# tinyduino-breakout-mk-4_3.net
KiCad netlist of a schematic drawn in EAGLE
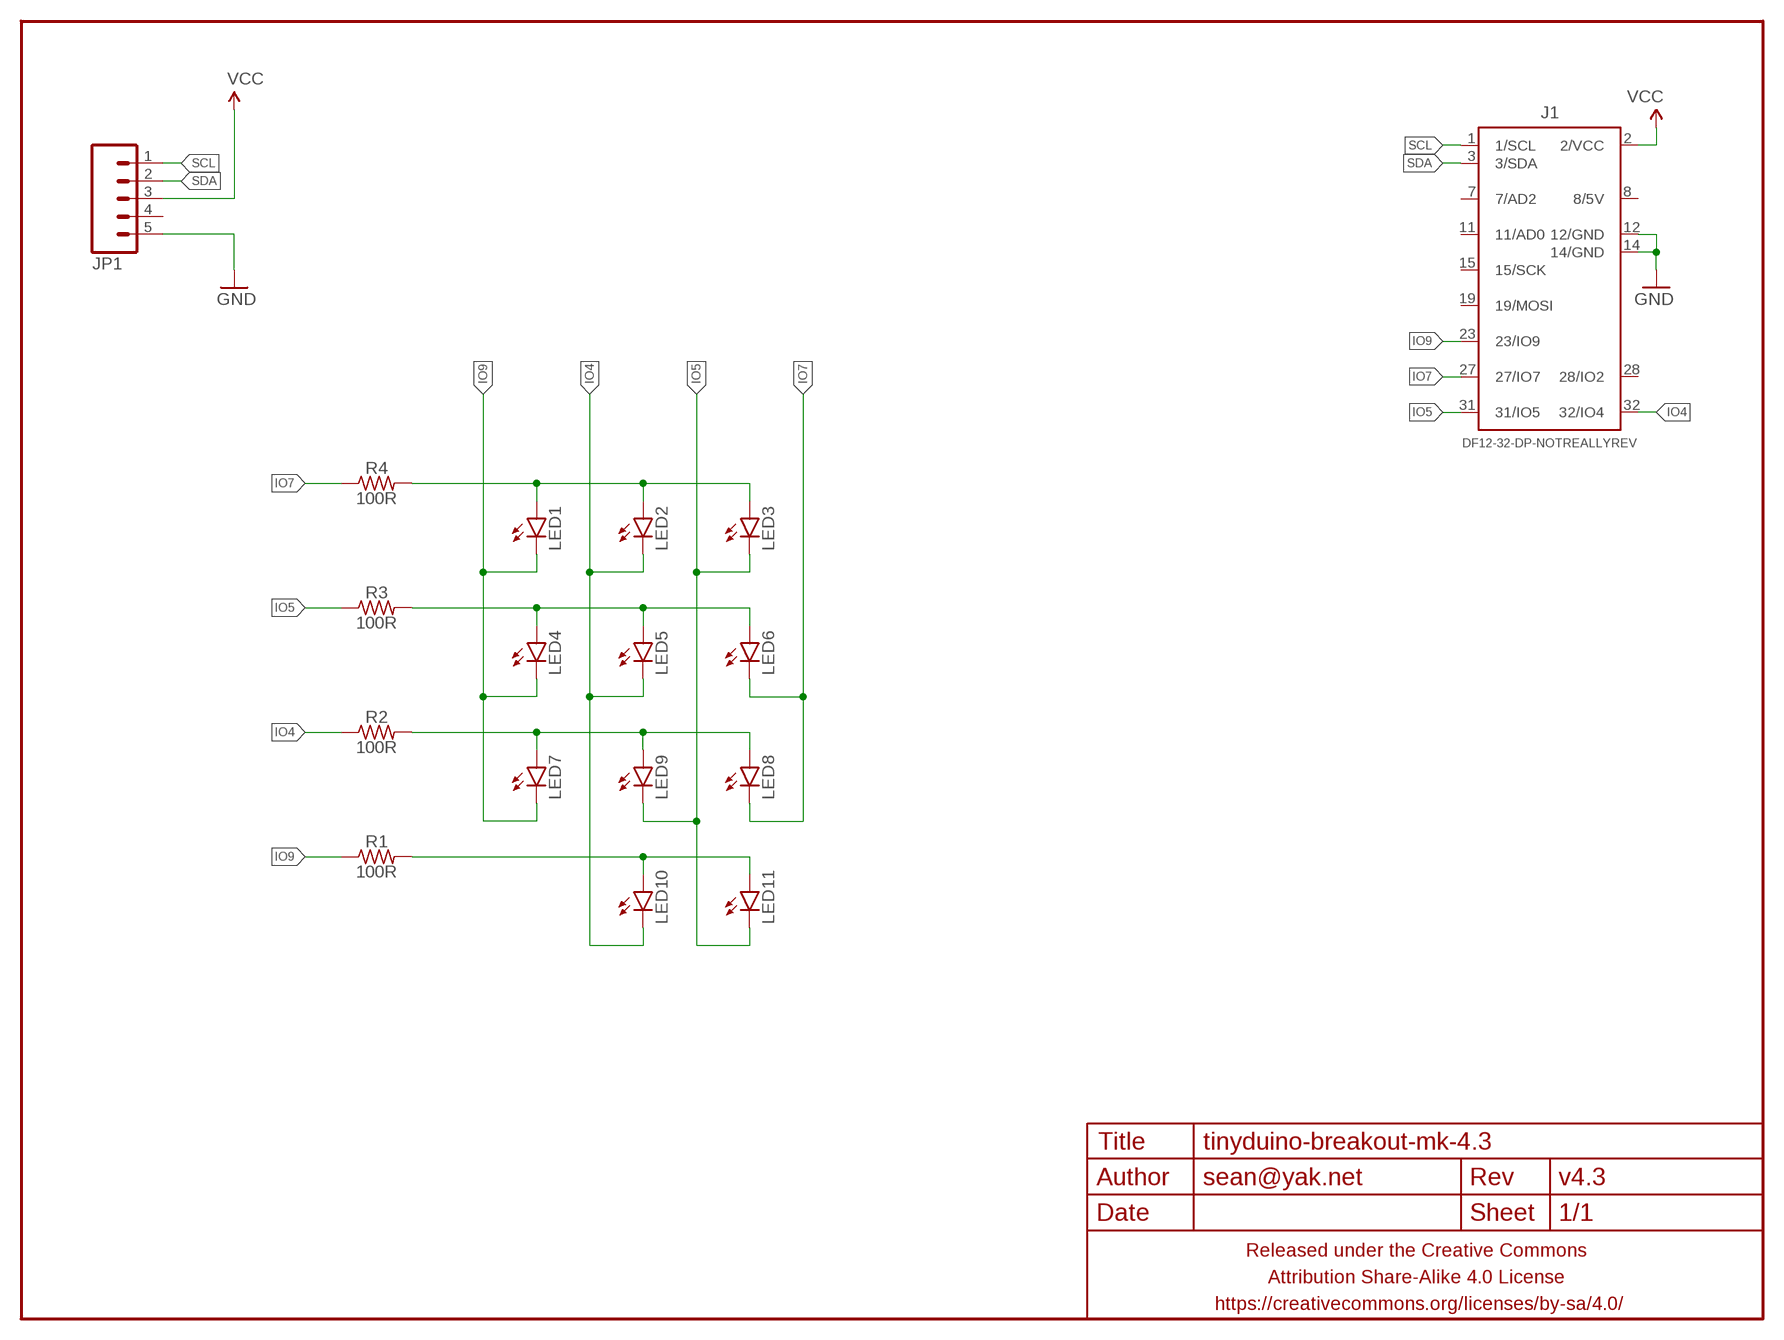
[diagram p0: schematic, sheet 1]

(export (version "E")
  (design (tool "Eeschema 10.0.6"))
  (components
    (comp (ref "FRAME1")
      (value "FRAME-LETTERNO_PACKAGE")
      (footprint "eagle-import:DUMMY")
      (fields (field (name "DESIGNER") "sean@yak.net") (field (name "VERSION") "v4.3"))
      (libsource (lib "eagle-import") (part "FRAME-LETTERNO_PACKAGE"))
    )
    (comp (ref "J1")
      (value "DF12-32-DP-NOTREALLYREV")
      (footprint "eagle-import:DF12-32-DP-I2C+EXTRA-REV")
      (libsource (lib "eagle-import") (part "DF12-32-DP-NOTREALLYREV"))
    )
    (comp (ref "JP1")
      (value "M05SMD-SHORT")
      (footprint "eagle-import:1X05-SMD-SHORT")
      (libsource (lib "eagle-import") (part "M05SMD-SHORT"))
    )
    (comp (ref "LED1")
      (value "LED0603")
      (footprint "eagle-import:LED-0603")
      (libsource (lib "eagle-import") (part "LED0603"))
    )
    (comp (ref "LED2")
      (value "LED0603")
      (footprint "eagle-import:LED-0603")
      (libsource (lib "eagle-import") (part "LED0603"))
    )
    (comp (ref "LED3")
      (value "LED0603")
      (footprint "eagle-import:LED-0603")
      (libsource (lib "eagle-import") (part "LED0603"))
    )
    (comp (ref "LED4")
      (value "LED0603")
      (footprint "eagle-import:LED-0603")
      (libsource (lib "eagle-import") (part "LED0603"))
    )
    (comp (ref "LED5")
      (value "LED0603")
      (footprint "eagle-import:LED-0603")
      (libsource (lib "eagle-import") (part "LED0603"))
    )
    (comp (ref "LED6")
      (value "LED0603")
      (footprint "eagle-import:LED-0603")
      (libsource (lib "eagle-import") (part "LED0603"))
    )
    (comp (ref "LED7")
      (value "LED0603")
      (footprint "eagle-import:LED-0603")
      (libsource (lib "eagle-import") (part "LED0603"))
    )
    (comp (ref "LED8")
      (value "LED0603")
      (footprint "eagle-import:LED-0603")
      (libsource (lib "eagle-import") (part "LED0603"))
    )
    (comp (ref "LED9")
      (value "LED0603")
      (footprint "eagle-import:LED-0603")
      (libsource (lib "eagle-import") (part "LED0603"))
    )
    (comp (ref "LED10")
      (value "LED0603")
      (footprint "eagle-import:LED-0603")
      (libsource (lib "eagle-import") (part "LED0603"))
    )
    (comp (ref "LED11")
      (value "LED0603")
      (footprint "eagle-import:LED-0603")
      (libsource (lib "eagle-import") (part "LED0603"))
    )
    (comp (ref "R1")
      (value "100R")
      (footprint "eagle-import:R0603")
      (libsource (lib "eagle-import") (part "RESISTORR0603"))
    )
    (comp (ref "R2")
      (value "100R")
      (footprint "eagle-import:R0603")
      (libsource (lib "eagle-import") (part "RESISTORR0603"))
    )
    (comp (ref "R3")
      (value "100R")
      (footprint "eagle-import:R0603")
      (libsource (lib "eagle-import") (part "RESISTORR0603"))
    )
    (comp (ref "R4")
      (value "100R")
      (footprint "eagle-import:R0603")
      (libsource (lib "eagle-import") (part "RESISTORR0603"))
    )
  )
  (nets
    (net (code "1") (name "GND") (class "Default")
      (node (ref "J1") (pin "12") (pinfunction "12/GND_12") (pintype "bidirectional"))
      (node (ref "J1") (pin "14") (pinfunction "14/GND_14") (pintype "bidirectional"))
      (node (ref "JP1") (pin "5") (pinfunction "5_5") (pintype "passive"))
    )
    (net (code "2") (name "IO4") (class "Default")
      (node (ref "J1") (pin "32") (pinfunction "32/IO4_32") (pintype "bidirectional"))
      (node (ref "LED10") (pin "C") (pinfunction "C_C") (pintype "passive"))
      (node (ref "LED2") (pin "C") (pinfunction "C_C") (pintype "passive"))
      (node (ref "LED5") (pin "C") (pinfunction "C_C") (pintype "passive"))
      (node (ref "R2") (pin "1") (pinfunction "1_1") (pintype "passive"))
    )
    (net (code "3") (name "IO5") (class "Default")
      (node (ref "J1") (pin "31") (pinfunction "31/IO5_31") (pintype "bidirectional"))
      (node (ref "LED11") (pin "C") (pinfunction "C_C") (pintype "passive"))
      (node (ref "LED3") (pin "C") (pinfunction "C_C") (pintype "passive"))
      (node (ref "LED9") (pin "C") (pinfunction "C_C") (pintype "passive"))
      (node (ref "R3") (pin "1") (pinfunction "1_1") (pintype "passive"))
    )
    (net (code "4") (name "IO7") (class "Default")
      (node (ref "J1") (pin "27") (pinfunction "27/IO7_27") (pintype "bidirectional"))
      (node (ref "LED6") (pin "C") (pinfunction "C_C") (pintype "passive"))
      (node (ref "LED8") (pin "C") (pinfunction "C_C") (pintype "passive"))
      (node (ref "R4") (pin "1") (pinfunction "1_1") (pintype "passive"))
    )
    (net (code "5") (name "IO9") (class "Default")
      (node (ref "J1") (pin "23") (pinfunction "23/IO9_23") (pintype "bidirectional"))
      (node (ref "LED1") (pin "C") (pinfunction "C_C") (pintype "passive"))
      (node (ref "LED4") (pin "C") (pinfunction "C_C") (pintype "passive"))
      (node (ref "LED7") (pin "C") (pinfunction "C_C") (pintype "passive"))
      (node (ref "R1") (pin "1") (pinfunction "1_1") (pintype "passive"))
    )
    (net (code "6") (name "Net-(LED1-PadA)") (class "Default")
      (node (ref "LED1") (pin "A") (pinfunction "A_A") (pintype "passive"))
      (node (ref "LED2") (pin "A") (pinfunction "A_A") (pintype "passive"))
      (node (ref "LED3") (pin "A") (pinfunction "A_A") (pintype "passive"))
      (node (ref "R4") (pin "2") (pinfunction "2_2") (pintype "passive"))
    )
    (net (code "7") (name "Net-(LED4-PadA)") (class "Default")
      (node (ref "LED4") (pin "A") (pinfunction "A_A") (pintype "passive"))
      (node (ref "LED5") (pin "A") (pinfunction "A_A") (pintype "passive"))
      (node (ref "LED6") (pin "A") (pinfunction "A_A") (pintype "passive"))
      (node (ref "R3") (pin "2") (pinfunction "2_2") (pintype "passive"))
    )
    (net (code "8") (name "Net-(LED7-PadA)") (class "Default")
      (node (ref "LED7") (pin "A") (pinfunction "A_A") (pintype "passive"))
      (node (ref "LED8") (pin "A") (pinfunction "A_A") (pintype "passive"))
      (node (ref "LED9") (pin "A") (pinfunction "A_A") (pintype "passive"))
      (node (ref "R2") (pin "2") (pinfunction "2_2") (pintype "passive"))
    )
    (net (code "9") (name "Net-(LED10-PadA)") (class "Default")
      (node (ref "LED10") (pin "A") (pinfunction "A_A") (pintype "passive"))
      (node (ref "LED11") (pin "A") (pinfunction "A_A") (pintype "passive"))
      (node (ref "R1") (pin "2") (pinfunction "2_2") (pintype "passive"))
    )
    (net (code "10") (name "SCL") (class "Default")
      (node (ref "J1") (pin "1") (pinfunction "1/SCL_1") (pintype "bidirectional"))
      (node (ref "JP1") (pin "1") (pinfunction "1_1") (pintype "passive"))
    )
    (net (code "11") (name "SDA") (class "Default")
      (node (ref "J1") (pin "3") (pinfunction "3/SDA_3") (pintype "bidirectional"))
      (node (ref "JP1") (pin "2") (pinfunction "2_2") (pintype "passive"))
    )
    (net (code "12") (name "VCC") (class "Default")
      (node (ref "J1") (pin "2") (pinfunction "2/VCC_2") (pintype "bidirectional"))
      (node (ref "JP1") (pin "3") (pinfunction "3_3") (pintype "passive"))
    )
    (net (code "13") (name "unconnected-(J1-7{slash}AD2-Pad7)") (class "Default")
      (node (ref "J1") (pin "7") (pinfunction "7/AD2_7") (pintype "bidirectional"))
    )
    (net (code "14") (name "unconnected-(J1-8{slash}5V-Pad8)") (class "Default")
      (node (ref "J1") (pin "8") (pinfunction "8/5V_8") (pintype "bidirectional"))
    )
    (net (code "15") (name "unconnected-(J1-11{slash}AD0-Pad11)") (class "Default")
      (node (ref "J1") (pin "11") (pinfunction "11/AD0_11") (pintype "bidirectional"))
    )
    (net (code "16") (name "unconnected-(J1-15{slash}SCK-Pad15)") (class "Default")
      (node (ref "J1") (pin "15") (pinfunction "15/SCK_15") (pintype "bidirectional"))
    )
    (net (code "17") (name "unconnected-(J1-19{slash}MOSI-Pad19)") (class "Default")
      (node (ref "J1") (pin "19") (pinfunction "19/MOSI_19") (pintype "bidirectional"))
    )
    (net (code "18") (name "unconnected-(J1-28{slash}IO2-Pad28)") (class "Default")
      (node (ref "J1") (pin "28") (pinfunction "28/IO2_28") (pintype "bidirectional"))
    )
    (net (code "19") (name "unconnected-(JP1-Pad4)") (class "Default")
      (node (ref "JP1") (pin "4") (pinfunction "4_4") (pintype "passive"))
    )
  )
)
